# Power_Selection_Archived.net
KiCad netlist of a schematic drawn in Altium Designer
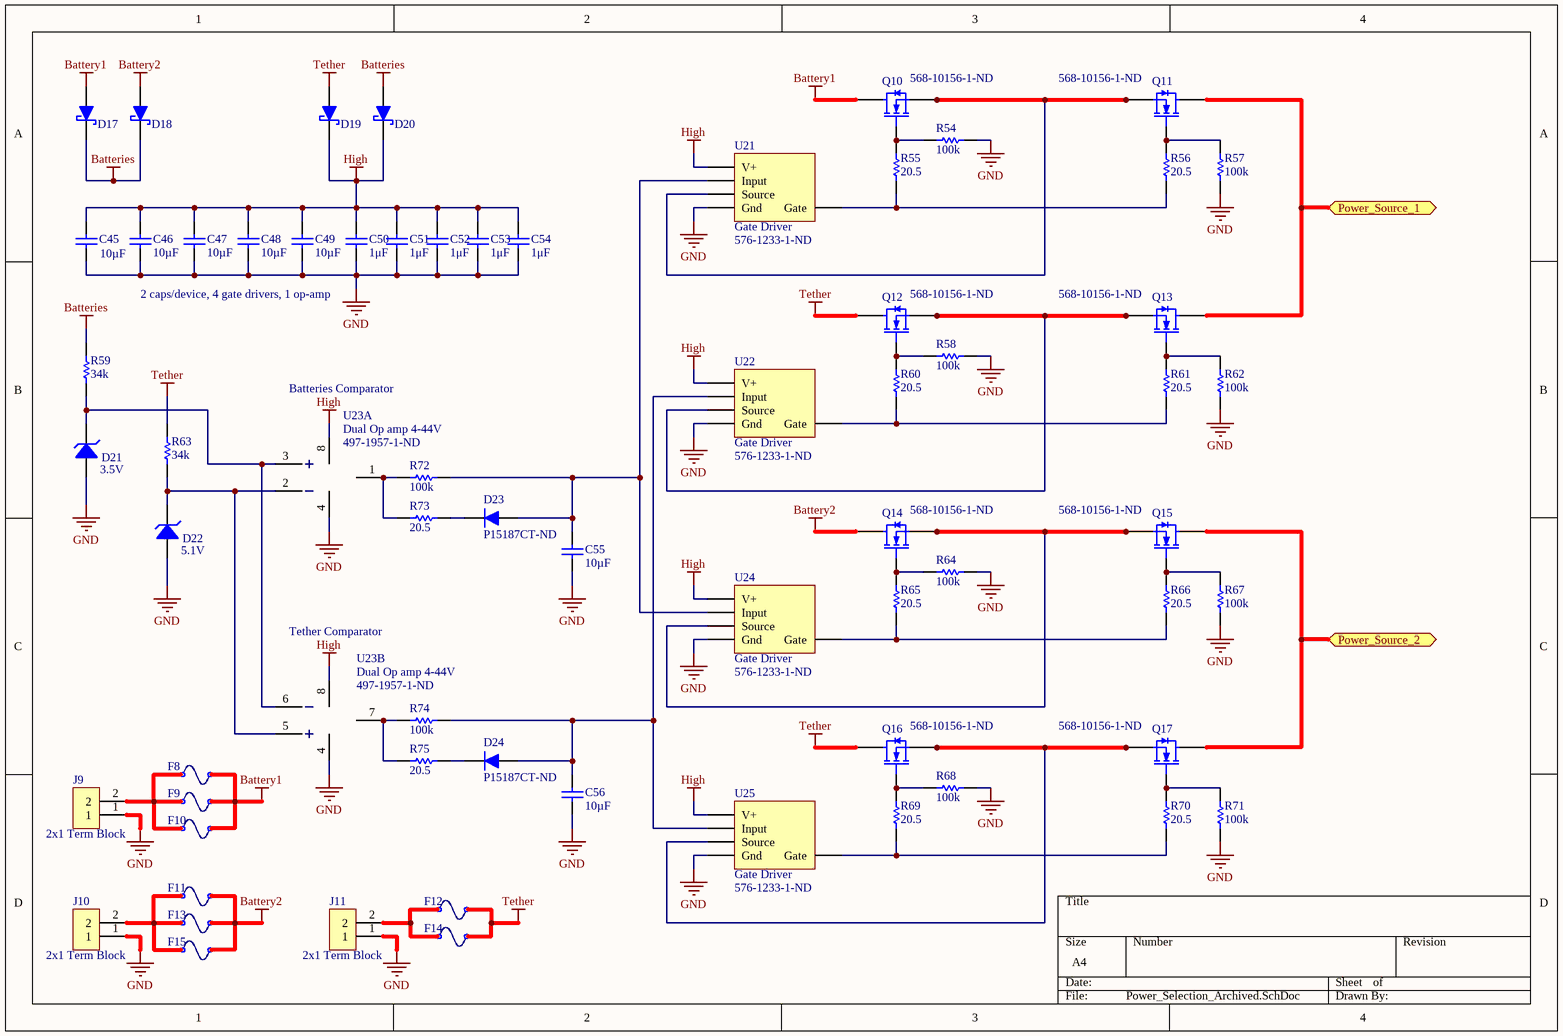
[diagram p0: Power_Selection_Archived.SchDoc]

(export (version "E")
  (design (tool "Eeschema 10.0.6"))
  (components
    (comp (ref "C45")
      (value "10µF")
      (footprint "CAPC3216N(1206\")")
      (description "Capacitor, Ceramic, 50V, +/- 10%, 1206 SMD, X5R")
      (fields (field (name "PUBLISHER") "AUVic"))
      (libsource (lib "AUVic_Integrated_Library_Capacitors") (part "10uF 50V 1206 SMD, Ceramic"))
    )
    (comp (ref "C46")
      (value "10µF")
      (footprint "CAPC3216N(1206\")")
      (description "Capacitor, Ceramic, 50V, +/- 10%, 1206 SMD, X5R")
      (fields (field (name "PUBLISHER") "AUVic"))
      (libsource (lib "AUVic_Integrated_Library_Capacitors") (part "10uF 50V 1206 SMD, Ceramic"))
    )
    (comp (ref "C47")
      (value "10µF")
      (footprint "CAPC3216N(1206\")")
      (description "Capacitor, Ceramic, 50V, +/- 10%, 1206 SMD, X5R")
      (fields (field (name "PUBLISHER") "AUVic"))
      (libsource (lib "AUVic_Integrated_Library_Capacitors") (part "10uF 50V 1206 SMD, Ceramic"))
    )
    (comp (ref "C48")
      (value "10µF")
      (footprint "CAPC3216N(1206\")")
      (description "Capacitor, Ceramic, 50V, +/- 10%, 1206 SMD, X5R")
      (fields (field (name "PUBLISHER") "AUVic"))
      (libsource (lib "AUVic_Integrated_Library_Capacitors") (part "10uF 50V 1206 SMD, Ceramic"))
    )
    (comp (ref "C49")
      (value "10µF")
      (footprint "CAPC3216N(1206\")")
      (description "Capacitor, Ceramic, 50V, +/- 10%, 1206 SMD, X5R")
      (fields (field (name "PUBLISHER") "AUVic"))
      (libsource (lib "AUVic_Integrated_Library_Capacitors") (part "10uF 50V 1206 SMD, Ceramic"))
    )
    (comp (ref "C50")
      (value "1μF")
      (footprint "CAPC1608N(0603\")")
      (description "Capacitor, Ceramic, 50V, +/- 10%, 0603 SMD, X5R")
      (fields (field (name "CREATED BY") "Lyden Smith"))
      (libsource (lib "AUVic_Integrated_Library_Capacitors") (part "1uF 50V 0603 SMD, Ceramic"))
    )
    (comp (ref "C51")
      (value "1μF")
      (footprint "CAPC1608N(0603\")")
      (description "Capacitor, Ceramic, 50V, +/- 10%, 0603 SMD, X5R")
      (fields (field (name "CREATED BY") "Lyden Smith"))
      (libsource (lib "AUVic_Integrated_Library_Capacitors") (part "1uF 50V 0603 SMD, Ceramic"))
    )
    (comp (ref "C52")
      (value "1μF")
      (footprint "CAPC1608N(0603\")")
      (description "Capacitor, Ceramic, 50V, +/- 10%, 0603 SMD, X5R")
      (fields (field (name "CREATED BY") "Lyden Smith"))
      (libsource (lib "AUVic_Integrated_Library_Capacitors") (part "1uF 50V 0603 SMD, Ceramic"))
    )
    (comp (ref "C53")
      (value "1μF")
      (footprint "CAPC1608N(0603\")")
      (description "Capacitor, Ceramic, 50V, +/- 10%, 0603 SMD, X5R")
      (fields (field (name "CREATED BY") "Lyden Smith"))
      (libsource (lib "AUVic_Integrated_Library_Capacitors") (part "1uF 50V 0603 SMD, Ceramic"))
    )
    (comp (ref "C54")
      (value "1μF")
      (footprint "CAPC1608N(0603\")")
      (description "Capacitor, Ceramic, 50V, +/- 10%, 0603 SMD, X5R")
      (fields (field (name "CREATED BY") "Lyden Smith"))
      (libsource (lib "AUVic_Integrated_Library_Capacitors") (part "1uF 50V 0603 SMD, Ceramic"))
    )
    (comp (ref "C55")
      (value "10µF")
      (footprint "CAPC3216N(1206\")")
      (description "Capacitor, Ceramic, 50V, +/- 10%, 1206 SMD, X5R")
      (fields (field (name "PUBLISHER") "AUVic"))
      (libsource (lib "AUVic_Integrated_Library_Capacitors") (part "10uF 50V 1206 SMD, Ceramic"))
    )
    (comp (ref "C56")
      (value "10µF")
      (footprint "CAPC3216N(1206\")")
      (description "Capacitor, Ceramic, 50V, +/- 10%, 1206 SMD, X5R")
      (fields (field (name "PUBLISHER") "AUVic"))
      (libsource (lib "AUVic_Integrated_Library_Capacitors") (part "10uF 50V 1206 SMD, Ceramic"))
    )
    (comp (ref "D17")
      (value "CUS08F30H3FCT-ND")
      (footprint "SC-76")
      (description "Diode, Schottky, 30V, 800mA")
      (fields (field (name "CREATED BY") "Andy Bates") (field (name "PUBLISHER") "AUVic"))
      (libsource (lib "AUVic_Integrated_Library_Diodes") (part "CUS08F30H3FCT-ND"))
    )
    (comp (ref "D18")
      (value "CUS08F30H3FCT-ND")
      (footprint "SC-76")
      (description "Diode, Schottky, 30V, 800mA")
      (fields (field (name "CREATED BY") "Andy Bates") (field (name "PUBLISHER") "AUVic"))
      (libsource (lib "AUVic_Integrated_Library_Diodes") (part "CUS08F30H3FCT-ND"))
    )
    (comp (ref "D19")
      (value "CUS08F30H3FCT-ND")
      (footprint "SC-76")
      (description "Diode, Schottky, 30V, 800mA")
      (fields (field (name "CREATED BY") "Andy Bates") (field (name "PUBLISHER") "AUVic"))
      (libsource (lib "AUVic_Integrated_Library_Diodes") (part "CUS08F30H3FCT-ND"))
    )
    (comp (ref "D20")
      (value "CUS08F30H3FCT-ND")
      (footprint "SC-76")
      (description "Diode, Schottky, 30V, 800mA")
      (fields (field (name "CREATED BY") "Andy Bates") (field (name "PUBLISHER") "AUVic"))
      (libsource (lib "AUVic_Integrated_Library_Diodes") (part "CUS08F30H3FCT-ND"))
    )
    (comp (ref "D21")
      (value "UCLAMP3301H.TCT")
      (footprint "SODFL160X70-2N")
      (description "Diode, TVS, 3.5V")
      (fields
        (field (name "MANUFACTURER") "Semtech Corporation")
        (field (name "VOLTAGE - BREAKDOWN (MIN)") "3.5V")
      )
      (libsource (lib "AUVic_Integrated_Library_Diodes") (part "UCLAMP3301H.TCT"))
    )
    (comp (ref "D22")
      (value "MM3Z5V1ST1G")
      (description "DIODE ZENER 5.1V 200MW SOD323")
      (fields
        (field (name "MANUFACTURER") "ON Semiconductor")
        (field (name "VOLTAGE - ZENER (NOM) (VZ)") "5.1V")
        (field (name "TOLERANCE") "±2%")
      )
      (libsource (lib "AUVic_Integrated_Library_Diodes") (part "MM3Z5V1ST1G"))
    )
    (comp (ref "D23")
      (value "DA2S10400L, SOD323F / SC-90")
      (footprint "SODFL535X110-2N")
      (fields
        (field (name "SUPPLIER PART NUMBER 1") "P15187CT-ND")
        (field (name "CREATED BY") "Andy Bates")
        (field (name "PUBLISHER") "AUVic")
      )
      (libsource (lib "AUVic_Integrated_Library_Diodes") (part "DA2S10400L, SOD323F / SC-90"))
    )
    (comp (ref "D24")
      (value "DA2S10400L, SOD323F / SC-90")
      (footprint "SODFL535X110-2N")
      (fields
        (field (name "SUPPLIER PART NUMBER 1") "P15187CT-ND")
        (field (name "CREATED BY") "Andy Bates")
        (field (name "PUBLISHER") "AUVic")
      )
      (libsource (lib "AUVic_Integrated_Library_Diodes") (part "DA2S10400L, SOD323F / SC-90"))
    )
    (comp (ref "F8")
      (value "MINI")
      (footprint "MINI BLADE FUSEHOLDER")
      (description "Blade Fuse Holder, 30A")
      (fields (field (name "CREATED BY") "Lyden Smith"))
      (libsource (lib "AUVic_Integrated_Library_Fuses") (part "MINI, ATC, ATO, etc. Blade Fuse"))
    )
    (comp (ref "F9")
      (value "MINI")
      (footprint "MINI BLADE FUSEHOLDER")
      (description "Blade Fuse Holder, 30A")
      (fields (field (name "CREATED BY") "Lyden Smith"))
      (libsource (lib "AUVic_Integrated_Library_Fuses") (part "MINI, ATC, ATO, etc. Blade Fuse"))
    )
    (comp (ref "F10")
      (value "MINI")
      (footprint "MINI BLADE FUSEHOLDER")
      (description "Blade Fuse Holder, 30A")
      (fields (field (name "CREATED BY") "Lyden Smith"))
      (libsource (lib "AUVic_Integrated_Library_Fuses") (part "MINI, ATC, ATO, etc. Blade Fuse"))
    )
    (comp (ref "F11")
      (value "MINI")
      (footprint "MINI BLADE FUSEHOLDER")
      (description "Blade Fuse Holder, 30A")
      (fields (field (name "CREATED BY") "Lyden Smith"))
      (libsource (lib "AUVic_Integrated_Library_Fuses") (part "MINI, ATC, ATO, etc. Blade Fuse"))
    )
    (comp (ref "F12")
      (value "MINI")
      (footprint "MINI BLADE FUSEHOLDER")
      (description "Blade Fuse Holder, 30A")
      (fields (field (name "CREATED BY") "Lyden Smith"))
      (libsource (lib "AUVic_Integrated_Library_Fuses") (part "MINI, ATC, ATO, etc. Blade Fuse"))
    )
    (comp (ref "F13")
      (value "MINI")
      (footprint "MINI BLADE FUSEHOLDER")
      (description "Blade Fuse Holder, 30A")
      (fields (field (name "CREATED BY") "Lyden Smith"))
      (libsource (lib "AUVic_Integrated_Library_Fuses") (part "MINI, ATC, ATO, etc. Blade Fuse"))
    )
    (comp (ref "F14")
      (value "MINI")
      (footprint "MINI BLADE FUSEHOLDER")
      (description "Blade Fuse Holder, 30A")
      (fields (field (name "CREATED BY") "Lyden Smith"))
      (libsource (lib "AUVic_Integrated_Library_Fuses") (part "MINI, ATC, ATO, etc. Blade Fuse"))
    )
    (comp (ref "F15")
      (value "MINI")
      (footprint "MINI BLADE FUSEHOLDER")
      (description "Blade Fuse Holder, 30A")
      (fields (field (name "CREATED BY") "Lyden Smith"))
      (libsource (lib "AUVic_Integrated_Library_Fuses") (part "MINI, ATC, ATO, etc. Blade Fuse"))
    )
    (comp (ref "J9")
      (value "2x1 Term Block")
      (footprint "2x1 Terminal Blocks EM2929")
      (fields (field (name "MADE BY") "Lyden Smith"))
      (libsource (lib "AUVic_Integrated_Library_Connectors") (part "2x1 Terminal Block, 65A, 6-20AWG"))
    )
    (comp (ref "J10")
      (value "2x1 Term Block")
      (footprint "2x1 Terminal Blocks EM2929")
      (fields (field (name "MADE BY") "Lyden Smith"))
      (libsource (lib "AUVic_Integrated_Library_Connectors") (part "2x1 Terminal Block, 65A, 6-20AWG"))
    )
    (comp (ref "J11")
      (value "2x1 Term Block")
      (footprint "2x1 Terminal Blocks EM2929")
      (fields (field (name "MADE BY") "Lyden Smith"))
      (libsource (lib "AUVic_Integrated_Library_Connectors") (part "2x1 Terminal Block, 65A, 6-20AWG"))
    )
    (comp (ref "Q10")
      (value "MOSFET N-Channel, 40V, 100A, 272W")
      (footprint "LFPAK-PowerSO8")
      (description "MOSFET N-Channel, 40V, 100A, 272W, Enh-Mode")
      (fields
        (field (name "MFG") "NXP Semiconductors")
        (field (name "SUPPLIER PART NUMBER 1") "568-10156-1-ND")
        (field (name "CREATED BY") "Ashwin Sira")
        (field (name "PUBLISHER") "AUVic")
        (field (name "REVIEWED_BY") "Ashwin Sira")
      )
      (libsource (lib "AUVic_Integrated_Library_Transistors") (part "MOSFET N-Channel, 40V, 100A, 272W"))
    )
    (comp (ref "Q11")
      (value "MOSFET N-Channel, 40V, 100A, 272W")
      (footprint "LFPAK-PowerSO8")
      (description "MOSFET N-Channel, 40V, 100A, 272W, Enh-Mode")
      (fields
        (field (name "MFG") "NXP Semiconductors")
        (field (name "SUPPLIER PART NUMBER 1") "568-10156-1-ND")
        (field (name "CREATED BY") "Ashwin Sira")
        (field (name "PUBLISHER") "AUVic")
        (field (name "REVIEWED_BY") "Ashwin Sira")
      )
      (libsource (lib "AUVic_Integrated_Library_Transistors") (part "MOSFET N-Channel, 40V, 100A, 272W"))
    )
    (comp (ref "Q12")
      (value "MOSFET N-Channel, 40V, 100A, 272W")
      (footprint "LFPAK-PowerSO8")
      (description "MOSFET N-Channel, 40V, 100A, 272W, Enh-Mode")
      (fields
        (field (name "MFG") "NXP Semiconductors")
        (field (name "SUPPLIER PART NUMBER 1") "568-10156-1-ND")
        (field (name "CREATED BY") "Ashwin Sira")
        (field (name "PUBLISHER") "AUVic")
        (field (name "REVIEWED_BY") "Ashwin Sira")
      )
      (libsource (lib "AUVic_Integrated_Library_Transistors") (part "MOSFET N-Channel, 40V, 100A, 272W"))
    )
    (comp (ref "Q13")
      (value "MOSFET N-Channel, 40V, 100A, 272W")
      (footprint "LFPAK-PowerSO8")
      (description "MOSFET N-Channel, 40V, 100A, 272W, Enh-Mode")
      (fields
        (field (name "MFG") "NXP Semiconductors")
        (field (name "SUPPLIER PART NUMBER 1") "568-10156-1-ND")
        (field (name "CREATED BY") "Ashwin Sira")
        (field (name "PUBLISHER") "AUVic")
        (field (name "REVIEWED_BY") "Ashwin Sira")
      )
      (libsource (lib "AUVic_Integrated_Library_Transistors") (part "MOSFET N-Channel, 40V, 100A, 272W"))
    )
    (comp (ref "Q14")
      (value "MOSFET N-Channel, 40V, 100A, 272W")
      (footprint "LFPAK-PowerSO8")
      (description "MOSFET N-Channel, 40V, 100A, 272W, Enh-Mode")
      (fields
        (field (name "MFG") "NXP Semiconductors")
        (field (name "SUPPLIER PART NUMBER 1") "568-10156-1-ND")
        (field (name "CREATED BY") "Ashwin Sira")
        (field (name "PUBLISHER") "AUVic")
        (field (name "REVIEWED_BY") "Ashwin Sira")
      )
      (libsource (lib "AUVic_Integrated_Library_Transistors") (part "MOSFET N-Channel, 40V, 100A, 272W"))
    )
    (comp (ref "Q15")
      (value "MOSFET N-Channel, 40V, 100A, 272W")
      (footprint "LFPAK-PowerSO8")
      (description "MOSFET N-Channel, 40V, 100A, 272W, Enh-Mode")
      (fields
        (field (name "MFG") "NXP Semiconductors")
        (field (name "SUPPLIER PART NUMBER 1") "568-10156-1-ND")
        (field (name "CREATED BY") "Ashwin Sira")
        (field (name "PUBLISHER") "AUVic")
        (field (name "REVIEWED_BY") "Ashwin Sira")
      )
      (libsource (lib "AUVic_Integrated_Library_Transistors") (part "MOSFET N-Channel, 40V, 100A, 272W"))
    )
    (comp (ref "Q16")
      (value "MOSFET N-Channel, 40V, 100A, 272W")
      (footprint "LFPAK-PowerSO8")
      (description "MOSFET N-Channel, 40V, 100A, 272W, Enh-Mode")
      (fields
        (field (name "MFG") "NXP Semiconductors")
        (field (name "SUPPLIER PART NUMBER 1") "568-10156-1-ND")
        (field (name "CREATED BY") "Ashwin Sira")
        (field (name "PUBLISHER") "AUVic")
        (field (name "REVIEWED_BY") "Ashwin Sira")
      )
      (libsource (lib "AUVic_Integrated_Library_Transistors") (part "MOSFET N-Channel, 40V, 100A, 272W"))
    )
    (comp (ref "Q17")
      (value "MOSFET N-Channel, 40V, 100A, 272W")
      (footprint "LFPAK-PowerSO8")
      (description "MOSFET N-Channel, 40V, 100A, 272W, Enh-Mode")
      (fields
        (field (name "MFG") "NXP Semiconductors")
        (field (name "SUPPLIER PART NUMBER 1") "568-10156-1-ND")
        (field (name "CREATED BY") "Ashwin Sira")
        (field (name "PUBLISHER") "AUVic")
        (field (name "REVIEWED_BY") "Ashwin Sira")
      )
      (libsource (lib "AUVic_Integrated_Library_Transistors") (part "MOSFET N-Channel, 40V, 100A, 272W"))
    )
    (comp (ref "R54")
      (value "100k")
      (footprint "RESC2012N(0805\")")
      (description "100kR, 1%, 1/4W, 0805 SMD")
      (fields (field (name "MADE BY") "Ashwin Sira"))
      (libsource (lib "AUVic_Integrated_Library_Resistors") (part "100kR, 1%, 1/4W, 0805 SMD"))
    )
    (comp (ref "R55")
      (value "20.5")
      (footprint "RESC1608N(0603\")")
      (description "20.5 Ohm, 1%, 1/10W , 0603, SMD")
      (fields (field (name "CREATED BY") "Gabriel Green") (field (name "PUBLISHER") "AUVic"))
      (libsource (lib "AUVic_Integrated_Library_Resistors") (part "20.5 Ohm, 1%, 1/10W , 0603, SMD"))
    )
    (comp (ref "R56")
      (value "20.5")
      (footprint "RESC1608N(0603\")")
      (description "20.5 Ohm, 1%, 1/10W , 0603, SMD")
      (fields (field (name "CREATED BY") "Gabriel Green") (field (name "PUBLISHER") "AUVic"))
      (libsource (lib "AUVic_Integrated_Library_Resistors") (part "20.5 Ohm, 1%, 1/10W , 0603, SMD"))
    )
    (comp (ref "R57")
      (value "100k")
      (footprint "RESC2012N(0805\")")
      (description "100kR, 1%, 1/4W, 0805 SMD")
      (fields (field (name "MADE BY") "Ashwin Sira"))
      (libsource (lib "AUVic_Integrated_Library_Resistors") (part "100kR, 1%, 1/4W, 0805 SMD"))
    )
    (comp (ref "R58")
      (value "100k")
      (footprint "RESC2012N(0805\")")
      (description "100kR, 1%, 1/4W, 0805 SMD")
      (fields (field (name "MADE BY") "Ashwin Sira"))
      (libsource (lib "AUVic_Integrated_Library_Resistors") (part "100kR, 1%, 1/4W, 0805 SMD"))
    )
    (comp (ref "R59")
      (value "34k")
      (footprint "RESC1608N(0603\")")
      (description "RES 34K OHM 1/10W 1% 0603 SMD")
      (fields
        (field (name "MANUFACTURER") "Yageo")
        (field (name "MANUFACTURER PART NUMBER") "RC0603FR-0734KL")
      )
      (libsource (lib "AUVic_Integrated_Library_Resistors") (part "34kR, 1%, 1/10W, 0603"))
    )
    (comp (ref "R60")
      (value "20.5")
      (footprint "RESC1608N(0603\")")
      (description "20.5 Ohm, 1%, 1/10W , 0603, SMD")
      (fields (field (name "CREATED BY") "Gabriel Green") (field (name "PUBLISHER") "AUVic"))
      (libsource (lib "AUVic_Integrated_Library_Resistors") (part "20.5 Ohm, 1%, 1/10W , 0603, SMD"))
    )
    (comp (ref "R61")
      (value "20.5")
      (footprint "RESC1608N(0603\")")
      (description "20.5 Ohm, 1%, 1/10W , 0603, SMD")
      (fields (field (name "CREATED BY") "Gabriel Green") (field (name "PUBLISHER") "AUVic"))
      (libsource (lib "AUVic_Integrated_Library_Resistors") (part "20.5 Ohm, 1%, 1/10W , 0603, SMD"))
    )
    (comp (ref "R62")
      (value "100k")
      (footprint "RESC2012N(0805\")")
      (description "100kR, 1%, 1/4W, 0805 SMD")
      (fields (field (name "MADE BY") "Ashwin Sira"))
      (libsource (lib "AUVic_Integrated_Library_Resistors") (part "100kR, 1%, 1/4W, 0805 SMD"))
    )
    (comp (ref "R63")
      (value "34k")
      (footprint "RESC1608N(0603\")")
      (description "RES 34K OHM 1/10W 1% 0603 SMD")
      (fields
        (field (name "MANUFACTURER") "Yageo")
        (field (name "MANUFACTURER PART NUMBER") "RC0603FR-0734KL")
      )
      (libsource (lib "AUVic_Integrated_Library_Resistors") (part "34kR, 1%, 1/10W, 0603"))
    )
    (comp (ref "R64")
      (value "100k")
      (footprint "RESC2012N(0805\")")
      (description "100kR, 1%, 1/4W, 0805 SMD")
      (fields (field (name "MADE BY") "Ashwin Sira"))
      (libsource (lib "AUVic_Integrated_Library_Resistors") (part "100kR, 1%, 1/4W, 0805 SMD"))
    )
    (comp (ref "R65")
      (value "20.5")
      (footprint "RESC1608N(0603\")")
      (description "20.5 Ohm, 1%, 1/10W , 0603, SMD")
      (fields (field (name "CREATED BY") "Gabriel Green") (field (name "PUBLISHER") "AUVic"))
      (libsource (lib "AUVic_Integrated_Library_Resistors") (part "20.5 Ohm, 1%, 1/10W , 0603, SMD"))
    )
    (comp (ref "R66")
      (value "20.5")
      (footprint "RESC1608N(0603\")")
      (description "20.5 Ohm, 1%, 1/10W , 0603, SMD")
      (fields (field (name "CREATED BY") "Gabriel Green") (field (name "PUBLISHER") "AUVic"))
      (libsource (lib "AUVic_Integrated_Library_Resistors") (part "20.5 Ohm, 1%, 1/10W , 0603, SMD"))
    )
    (comp (ref "R67")
      (value "100k")
      (footprint "RESC2012N(0805\")")
      (description "100kR, 1%, 1/4W, 0805 SMD")
      (fields (field (name "MADE BY") "Ashwin Sira"))
      (libsource (lib "AUVic_Integrated_Library_Resistors") (part "100kR, 1%, 1/4W, 0805 SMD"))
    )
    (comp (ref "R68")
      (value "100k")
      (footprint "RESC2012N(0805\")")
      (description "100kR, 1%, 1/4W, 0805 SMD")
      (fields (field (name "MADE BY") "Ashwin Sira"))
      (libsource (lib "AUVic_Integrated_Library_Resistors") (part "100kR, 1%, 1/4W, 0805 SMD"))
    )
    (comp (ref "R69")
      (value "20.5")
      (footprint "RESC1608N(0603\")")
      (description "20.5 Ohm, 1%, 1/10W , 0603, SMD")
      (fields (field (name "CREATED BY") "Gabriel Green") (field (name "PUBLISHER") "AUVic"))
      (libsource (lib "AUVic_Integrated_Library_Resistors") (part "20.5 Ohm, 1%, 1/10W , 0603, SMD"))
    )
    (comp (ref "R70")
      (value "20.5")
      (footprint "RESC1608N(0603\")")
      (description "20.5 Ohm, 1%, 1/10W , 0603, SMD")
      (fields (field (name "CREATED BY") "Gabriel Green") (field (name "PUBLISHER") "AUVic"))
      (libsource (lib "AUVic_Integrated_Library_Resistors") (part "20.5 Ohm, 1%, 1/10W , 0603, SMD"))
    )
    (comp (ref "R71")
      (value "100k")
      (footprint "RESC2012N(0805\")")
      (description "100kR, 1%, 1/4W, 0805 SMD")
      (fields (field (name "MADE BY") "Ashwin Sira"))
      (libsource (lib "AUVic_Integrated_Library_Resistors") (part "100kR, 1%, 1/4W, 0805 SMD"))
    )
    (comp (ref "R72")
      (value "100k")
      (footprint "RESC2012N(0805\")")
      (description "100kR, 1%, 1/4W, 0805 SMD")
      (fields (field (name "MADE BY") "Ashwin Sira"))
      (libsource (lib "AUVic_Integrated_Library_Resistors") (part "100kR, 1%, 1/4W, 0805 SMD"))
    )
    (comp (ref "R73")
      (value "20.5")
      (footprint "RESC1608N(0603\")")
      (description "20.5 Ohm, 1%, 1/10W , 0603, SMD")
      (fields (field (name "CREATED BY") "Gabriel Green") (field (name "PUBLISHER") "AUVic"))
      (libsource (lib "AUVic_Integrated_Library_Resistors") (part "20.5 Ohm, 1%, 1/10W , 0603, SMD"))
    )
    (comp (ref "R74")
      (value "100k")
      (footprint "RESC2012N(0805\")")
      (description "100kR, 1%, 1/4W, 0805 SMD")
      (fields (field (name "MADE BY") "Ashwin Sira"))
      (libsource (lib "AUVic_Integrated_Library_Resistors") (part "100kR, 1%, 1/4W, 0805 SMD"))
    )
    (comp (ref "R75")
      (value "20.5")
      (footprint "RESC1608N(0603\")")
      (description "20.5 Ohm, 1%, 1/10W , 0603, SMD")
      (fields (field (name "CREATED BY") "Gabriel Green") (field (name "PUBLISHER") "AUVic"))
      (libsource (lib "AUVic_Integrated_Library_Resistors") (part "20.5 Ohm, 1%, 1/10W , 0603, SMD"))
    )
    (comp (ref "U21")
      (value "Gate Driver")
      (footprint "SOC 8")
      (fields (field (name "SUPPLIER PART NUMBER 1") "576-1233-1-ND"))
      (libsource (lib "AUVic_Integrated_Library_Gate_Drivers") (part "Gate Driver TTL Logic 3 - 30V"))
    )
    (comp (ref "U22")
      (value "Gate Driver")
      (footprint "SOC 8")
      (fields (field (name "SUPPLIER PART NUMBER 1") "576-1233-1-ND"))
      (libsource (lib "AUVic_Integrated_Library_Gate_Drivers") (part "Gate Driver TTL Logic 3 - 30V"))
    )
    (comp (ref "U23")
      (value "Dual Op amp 4-44V")
      (footprint "SOC-8")
      (description "MC33172")
      (fields (field (name "SUPPLIER PART NUMBER 2") "497-1957-1-ND") (field (name "MADE BY") "Andy Bates"))
      (libsource (lib "AUVic_Integrated_Library_Op_amps") (part "Dual Op amp 4-44V"))
    )
    (comp (ref "U24")
      (value "Gate Driver")
      (footprint "SOC 8")
      (fields (field (name "SUPPLIER PART NUMBER 1") "576-1233-1-ND"))
      (libsource (lib "AUVic_Integrated_Library_Gate_Drivers") (part "Gate Driver TTL Logic 3 - 30V"))
    )
    (comp (ref "U25")
      (value "Gate Driver")
      (footprint "SOC 8")
      (fields (field (name "SUPPLIER PART NUMBER 1") "576-1233-1-ND"))
      (libsource (lib "AUVic_Integrated_Library_Gate_Drivers") (part "Gate Driver TTL Logic 3 - 30V"))
    )
  )
  (nets
    (net (code "1") (name "/Power_Source_1") (class "Default")
      (node (ref "Q11") (pin "5") (pinfunction "Drain_5") (pintype "power_in"))
      (node (ref "Q13") (pin "5") (pinfunction "Drain_5") (pintype "power_in"))
    )
    (net (code "2") (name "/Power_Source_2") (class "Default")
      (node (ref "Q15") (pin "5") (pinfunction "Drain_5") (pintype "power_in"))
      (node (ref "Q17") (pin "5") (pinfunction "Drain_5") (pintype "power_in"))
    )
    (net (code "3") (name "Batteries") (class "Default")
      (node (ref "D17") (pin "K") (pinfunction "Cathode_K") (pintype "passive"))
      (node (ref "D18") (pin "K") (pinfunction "Cathode_K") (pintype "passive"))
      (node (ref "D20") (pin "A") (pinfunction "Anode_A") (pintype "passive"))
      (node (ref "R59") (pin "2") (pinfunction "2_2") (pintype "passive"))
    )
    (net (code "4") (name "Battery1") (class "Default")
      (node (ref "D17") (pin "A") (pinfunction "Anode_A") (pintype "passive"))
      (node (ref "F10") (pin "2") (pinfunction "2_2") (pintype "passive"))
      (node (ref "F8") (pin "2") (pinfunction "2_2") (pintype "passive"))
      (node (ref "F9") (pin "2") (pinfunction "2_2") (pintype "passive"))
      (node (ref "Q10") (pin "5") (pinfunction "Drain_5") (pintype "power_in"))
    )
    (net (code "5") (name "Battery2") (class "Default")
      (node (ref "D18") (pin "A") (pinfunction "Anode_A") (pintype "passive"))
      (node (ref "F11") (pin "2") (pinfunction "2_2") (pintype "passive"))
      (node (ref "F13") (pin "2") (pinfunction "2_2") (pintype "passive"))
      (node (ref "F15") (pin "2") (pinfunction "2_2") (pintype "passive"))
      (node (ref "Q14") (pin "5") (pinfunction "Drain_5") (pintype "power_in"))
    )
    (net (code "6") (name "GND") (class "Default")
      (node (ref "C45") (pin "1") (pinfunction "Anode_1") (pintype "passive"))
      (node (ref "C46") (pin "1") (pinfunction "Anode_1") (pintype "passive"))
      (node (ref "C47") (pin "1") (pinfunction "Anode_1") (pintype "passive"))
      (node (ref "C48") (pin "1") (pinfunction "Anode_1") (pintype "passive"))
      (node (ref "C49") (pin "1") (pinfunction "Anode_1") (pintype "passive"))
      (node (ref "C50") (pin "1") (pinfunction "Anode_1") (pintype "passive"))
      (node (ref "C51") (pin "1") (pinfunction "Anode_1") (pintype "passive"))
      (node (ref "C52") (pin "1") (pinfunction "Anode_1") (pintype "passive"))
      (node (ref "C53") (pin "1") (pinfunction "Anode_1") (pintype "passive"))
      (node (ref "C54") (pin "1") (pinfunction "Anode_1") (pintype "passive"))
      (node (ref "C55") (pin "1") (pinfunction "Anode_1") (pintype "passive"))
      (node (ref "C56") (pin "1") (pinfunction "Anode_1") (pintype "passive"))
      (node (ref "D21") (pin "1") (pinfunction "Anode_1") (pintype "passive"))
      (node (ref "D22") (pin "1") (pinfunction "Anode_1") (pintype "passive"))
      (node (ref "J10") (pin "1") (pinfunction "1_1") (pintype "passive"))
      (node (ref "J11") (pin "1") (pinfunction "1_1") (pintype "passive"))
      (node (ref "J9") (pin "1") (pinfunction "1_1") (pintype "passive"))
      (node (ref "R54") (pin "1") (pinfunction "1_1") (pintype "passive"))
      (node (ref "R57") (pin "2") (pinfunction "2_2") (pintype "passive"))
      (node (ref "R58") (pin "1") (pinfunction "1_1") (pintype "passive"))
      (node (ref "R62") (pin "2") (pinfunction "2_2") (pintype "passive"))
      (node (ref "R64") (pin "1") (pinfunction "1_1") (pintype "passive"))
      (node (ref "R67") (pin "2") (pinfunction "2_2") (pintype "passive"))
      (node (ref "R68") (pin "1") (pinfunction "1_1") (pintype "passive"))
      (node (ref "R71") (pin "2") (pinfunction "2_2") (pintype "passive"))
      (node (ref "U21") (pin "4") (pinfunction "Gnd_4") (pintype "passive"))
      (node (ref "U22") (pin "4") (pinfunction "Gnd_4") (pintype "passive"))
      (node (ref "U23") (pin "4") (pinfunction "Vcc-_4") (pintype "passive"))
      (node (ref "U24") (pin "4") (pinfunction "Gnd_4") (pintype "passive"))
      (node (ref "U25") (pin "4") (pinfunction "Gnd_4") (pintype "passive"))
    )
    (net (code "7") (name "High") (class "Default")
      (node (ref "C45") (pin "2") (pinfunction "Cathode_2") (pintype "passive"))
      (node (ref "C46") (pin "2") (pinfunction "Cathode_2") (pintype "passive"))
      (node (ref "C47") (pin "2") (pinfunction "Cathode_2") (pintype "passive"))
      (node (ref "C48") (pin "2") (pinfunction "Cathode_2") (pintype "passive"))
      (node (ref "C49") (pin "2") (pinfunction "Cathode_2") (pintype "passive"))
      (node (ref "C50") (pin "2") (pinfunction "Cathode_2") (pintype "passive"))
      (node (ref "C51") (pin "2") (pinfunction "Cathode_2") (pintype "passive"))
      (node (ref "C52") (pin "2") (pinfunction "Cathode_2") (pintype "passive"))
      (node (ref "C53") (pin "2") (pinfunction "Cathode_2") (pintype "passive"))
      (node (ref "C54") (pin "2") (pinfunction "Cathode_2") (pintype "passive"))
      (node (ref "D19") (pin "K") (pinfunction "Cathode_K") (pintype "passive"))
      (node (ref "D20") (pin "K") (pinfunction "Cathode_K") (pintype "passive"))
      (node (ref "U21") (pin "1") (pinfunction "V+_1") (pintype "passive"))
      (node (ref "U22") (pin "1") (pinfunction "V+_1") (pintype "passive"))
      (node (ref "U23") (pin "8") (pinfunction "Vcc+_8") (pintype "passive"))
      (node (ref "U24") (pin "1") (pinfunction "V+_1") (pintype "passive"))
      (node (ref "U25") (pin "1") (pinfunction "V+_1") (pintype "passive"))
    )
    (net (code "8") (name "Net-(C55-Cathode)") (class "Default")
      (node (ref "C55") (pin "2") (pinfunction "Cathode_2") (pintype "passive"))
      (node (ref "D23") (pin "1") (pinfunction "Anode_1") (pintype "passive"))
      (node (ref "R72") (pin "2") (pinfunction "2_2") (pintype "passive"))
      (node (ref "U21") (pin "2") (pinfunction "Input_2") (pintype "passive"))
      (node (ref "U24") (pin "2") (pinfunction "Input_2") (pintype "passive"))
    )
    (net (code "9") (name "Net-(C56-Cathode)") (class "Default")
      (node (ref "C56") (pin "2") (pinfunction "Cathode_2") (pintype "passive"))
      (node (ref "D24") (pin "1") (pinfunction "Anode_1") (pintype "passive"))
      (node (ref "R74") (pin "2") (pinfunction "2_2") (pintype "passive"))
      (node (ref "U22") (pin "2") (pinfunction "Input_2") (pintype "passive"))
      (node (ref "U25") (pin "2") (pinfunction "Input_2") (pintype "passive"))
    )
    (net (code "10") (name "Net-(D21-Cathode)") (class "Default")
      (node (ref "D21") (pin "2") (pinfunction "Cathode_2") (pintype "passive"))
      (node (ref "R59") (pin "1") (pinfunction "1_1") (pintype "passive"))
      (node (ref "U23") (pin "3") (pinfunction "V+_3") (pintype "passive"))
      (node (ref "U23") (pin "6") (pinfunction "V-_6") (pintype "passive"))
    )
    (net (code "11") (name "Net-(D22-Cathode)") (class "Default")
      (node (ref "D22") (pin "2") (pinfunction "Cathode_2") (pintype "passive"))
      (node (ref "R63") (pin "1") (pinfunction "1_1") (pintype "passive"))
      (node (ref "U23") (pin "2") (pinfunction "V-_2") (pintype "passive"))
      (node (ref "U23") (pin "5") (pinfunction "V+_5") (pintype "passive"))
    )
    (net (code "12") (name "Net-(D23-Cathode)") (class "Default")
      (node (ref "D23") (pin "2") (pinfunction "Cathode_2") (pintype "passive"))
      (node (ref "R73") (pin "2") (pinfunction "2_2") (pintype "passive"))
    )
    (net (code "13") (name "Net-(D24-Cathode)") (class "Default")
      (node (ref "D24") (pin "2") (pinfunction "Cathode_2") (pintype "passive"))
      (node (ref "R75") (pin "2") (pinfunction "2_2") (pintype "passive"))
    )
    (net (code "14") (name "Net-(F10-Pad1)") (class "Default")
      (node (ref "F10") (pin "1") (pinfunction "1_1") (pintype "passive"))
      (node (ref "F8") (pin "1") (pinfunction "1_1") (pintype "passive"))
      (node (ref "F9") (pin "1") (pinfunction "1_1") (pintype "passive"))
      (node (ref "J9") (pin "2") (pinfunction "2_2") (pintype "passive"))
    )
    (net (code "15") (name "Net-(F11-Pad1)") (class "Default")
      (node (ref "F11") (pin "1") (pinfunction "1_1") (pintype "passive"))
      (node (ref "F13") (pin "1") (pinfunction "1_1") (pintype "passive"))
      (node (ref "F15") (pin "1") (pinfunction "1_1") (pintype "passive"))
      (node (ref "J10") (pin "2") (pinfunction "2_2") (pintype "passive"))
    )
    (net (code "16") (name "Net-(F12-Pad1)") (class "Default")
      (node (ref "F12") (pin "1") (pinfunction "1_1") (pintype "passive"))
      (node (ref "F14") (pin "1") (pinfunction "1_1") (pintype "passive"))
      (node (ref "J11") (pin "2") (pinfunction "2_2") (pintype "passive"))
    )
    (net (code "17") (name "Net-(Q10-Gate)") (class "Default")
      (node (ref "Q10") (pin "4") (pinfunction "Gate_4") (pintype "power_in"))
      (node (ref "R54") (pin "2") (pinfunction "2_2") (pintype "passive"))
      (node (ref "R55") (pin "2") (pinfunction "2_2") (pintype "passive"))
    )
    (net (code "18") (name "Net-(Q11-Gate)") (class "Default")
      (node (ref "Q11") (pin "4") (pinfunction "Gate_4") (pintype "power_in"))
      (node (ref "R56") (pin "2") (pinfunction "2_2") (pintype "passive"))
      (node (ref "R57") (pin "1") (pinfunction "1_1") (pintype "passive"))
    )
    (net (code "19") (name "Net-(Q12-Gate)") (class "Default")
      (node (ref "Q12") (pin "4") (pinfunction "Gate_4") (pintype "power_in"))
      (node (ref "R58") (pin "2") (pinfunction "2_2") (pintype "passive"))
      (node (ref "R60") (pin "2") (pinfunction "2_2") (pintype "passive"))
    )
    (net (code "20") (name "Net-(Q13-Gate)") (class "Default")
      (node (ref "Q13") (pin "4") (pinfunction "Gate_4") (pintype "power_in"))
      (node (ref "R61") (pin "2") (pinfunction "2_2") (pintype "passive"))
      (node (ref "R62") (pin "1") (pinfunction "1_1") (pintype "passive"))
    )
    (net (code "21") (name "Net-(Q14-Gate)") (class "Default")
      (node (ref "Q14") (pin "4") (pinfunction "Gate_4") (pintype "power_in"))
      (node (ref "R64") (pin "2") (pinfunction "2_2") (pintype "passive"))
      (node (ref "R65") (pin "2") (pinfunction "2_2") (pintype "passive"))
    )
    (net (code "22") (name "Net-(Q15-Gate)") (class "Default")
      (node (ref "Q15") (pin "4") (pinfunction "Gate_4") (pintype "power_in"))
      (node (ref "R66") (pin "2") (pinfunction "2_2") (pintype "passive"))
      (node (ref "R67") (pin "1") (pinfunction "1_1") (pintype "passive"))
    )
    (net (code "23") (name "Net-(Q16-Gate)") (class "Default")
      (node (ref "Q16") (pin "4") (pinfunction "Gate_4") (pintype "power_in"))
      (node (ref "R68") (pin "2") (pinfunction "2_2") (pintype "passive"))
      (node (ref "R69") (pin "2") (pinfunction "2_2") (pintype "passive"))
    )
    (net (code "24") (name "Net-(Q17-Gate)") (class "Default")
      (node (ref "Q17") (pin "4") (pinfunction "Gate_4") (pintype "power_in"))
      (node (ref "R70") (pin "2") (pinfunction "2_2") (pintype "passive"))
      (node (ref "R71") (pin "1") (pinfunction "1_1") (pintype "passive"))
    )
    (net (code "25") (name "Net-(U21-Gate)") (class "Default")
      (node (ref "R55") (pin "1") (pinfunction "1_1") (pintype "passive"))
      (node (ref "R56") (pin "1") (pinfunction "1_1") (pintype "passive"))
      (node (ref "U21") (pin "5") (pinfunction "Gate_5") (pintype "passive"))
    )
    (net (code "26") (name "Net-(U21-Source)") (class "Default")
      (node (ref "Q10") (pin "1") (pinfunction "Source_1") (pintype "power_in"))
      (node (ref "Q10") (pin "2") (pinfunction "Source_2") (pintype "power_in"))
      (node (ref "Q10") (pin "3") (pinfunction "Source_3") (pintype "power_in"))
      (node (ref "Q11") (pin "1") (pinfunction "Source_1") (pintype "power_in"))
      (node (ref "Q11") (pin "2") (pinfunction "Source_2") (pintype "power_in"))
      (node (ref "Q11") (pin "3") (pinfunction "Source_3") (pintype "power_in"))
      (node (ref "U21") (pin "3") (pinfunction "Source_3") (pintype "passive"))
    )
    (net (code "27") (name "Net-(U22-Gate)") (class "Default")
      (node (ref "R60") (pin "1") (pinfunction "1_1") (pintype "passive"))
      (node (ref "R61") (pin "1") (pinfunction "1_1") (pintype "passive"))
      (node (ref "U22") (pin "5") (pinfunction "Gate_5") (pintype "passive"))
    )
    (net (code "28") (name "Net-(U22-Source)") (class "Default")
      (node (ref "Q12") (pin "1") (pinfunction "Source_1") (pintype "power_in"))
      (node (ref "Q12") (pin "2") (pinfunction "Source_2") (pintype "power_in"))
      (node (ref "Q12") (pin "3") (pinfunction "Source_3") (pintype "power_in"))
      (node (ref "Q13") (pin "1") (pinfunction "Source_1") (pintype "power_in"))
      (node (ref "Q13") (pin "2") (pinfunction "Source_2") (pintype "power_in"))
      (node (ref "Q13") (pin "3") (pinfunction "Source_3") (pintype "power_in"))
      (node (ref "U22") (pin "3") (pinfunction "Source_3") (pintype "passive"))
    )
    (net (code "29") (name "Net-(U23A-Out)") (class "Default")
      (node (ref "R72") (pin "1") (pinfunction "1_1") (pintype "passive"))
      (node (ref "R73") (pin "1") (pinfunction "1_1") (pintype "passive"))
      (node (ref "U23") (pin "1") (pinfunction "Out_1") (pintype "passive"))
    )
    (net (code "30") (name "Net-(U23B-Out)") (class "Default")
      (node (ref "R74") (pin "1") (pinfunction "1_1") (pintype "passive"))
      (node (ref "R75") (pin "1") (pinfunction "1_1") (pintype "passive"))
      (node (ref "U23") (pin "7") (pinfunction "Out_7") (pintype "passive"))
    )
    (net (code "31") (name "Net-(U24-Gate)") (class "Default")
      (node (ref "R65") (pin "1") (pinfunction "1_1") (pintype "passive"))
      (node (ref "R66") (pin "1") (pinfunction "1_1") (pintype "passive"))
      (node (ref "U24") (pin "5") (pinfunction "Gate_5") (pintype "passive"))
    )
    (net (code "32") (name "Net-(U24-Source)") (class "Default")
      (node (ref "Q14") (pin "1") (pinfunction "Source_1") (pintype "power_in"))
      (node (ref "Q14") (pin "2") (pinfunction "Source_2") (pintype "power_in"))
      (node (ref "Q14") (pin "3") (pinfunction "Source_3") (pintype "power_in"))
      (node (ref "Q15") (pin "1") (pinfunction "Source_1") (pintype "power_in"))
      (node (ref "Q15") (pin "2") (pinfunction "Source_2") (pintype "power_in"))
      (node (ref "Q15") (pin "3") (pinfunction "Source_3") (pintype "power_in"))
      (node (ref "U24") (pin "3") (pinfunction "Source_3") (pintype "passive"))
    )
    (net (code "33") (name "Net-(U25-Gate)") (class "Default")
      (node (ref "R69") (pin "1") (pinfunction "1_1") (pintype "passive"))
      (node (ref "R70") (pin "1") (pinfunction "1_1") (pintype "passive"))
      (node (ref "U25") (pin "5") (pinfunction "Gate_5") (pintype "passive"))
    )
    (net (code "34") (name "Net-(U25-Source)") (class "Default")
      (node (ref "Q16") (pin "1") (pinfunction "Source_1") (pintype "power_in"))
      (node (ref "Q16") (pin "2") (pinfunction "Source_2") (pintype "power_in"))
      (node (ref "Q16") (pin "3") (pinfunction "Source_3") (pintype "power_in"))
      (node (ref "Q17") (pin "1") (pinfunction "Source_1") (pintype "power_in"))
      (node (ref "Q17") (pin "2") (pinfunction "Source_2") (pintype "power_in"))
      (node (ref "Q17") (pin "3") (pinfunction "Source_3") (pintype "power_in"))
      (node (ref "U25") (pin "3") (pinfunction "Source_3") (pintype "passive"))
    )
    (net (code "35") (name "Tether") (class "Default")
      (node (ref "D19") (pin "A") (pinfunction "Anode_A") (pintype "passive"))
      (node (ref "F12") (pin "2") (pinfunction "2_2") (pintype "passive"))
      (node (ref "F14") (pin "2") (pinfunction "2_2") (pintype "passive"))
      (node (ref "Q12") (pin "5") (pinfunction "Drain_5") (pintype "power_in"))
      (node (ref "Q16") (pin "5") (pinfunction "Drain_5") (pintype "power_in"))
      (node (ref "R63") (pin "2") (pinfunction "2_2") (pintype "passive"))
    )
  )
)
